# PWM_CONTROL.net
KiCad netlist of a schematic drawn in Altium Designer
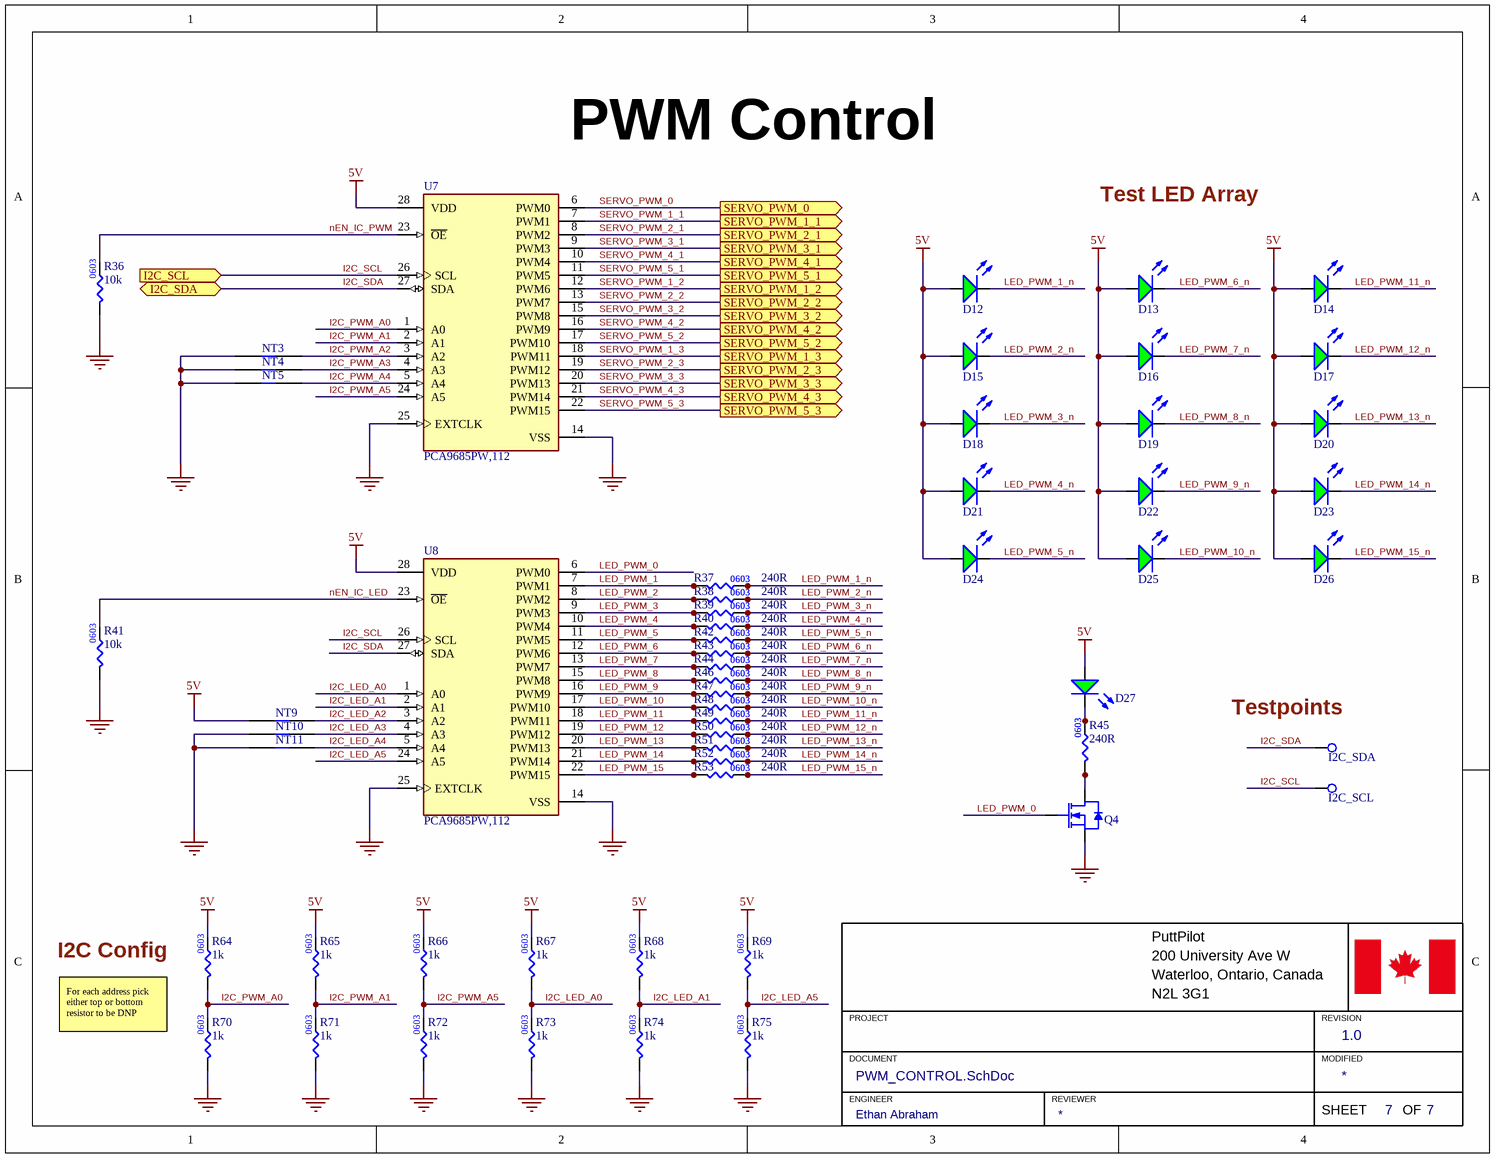
[diagram p0: PWM_CONTROL.SchDoc]

(export (version "E")
  (design (tool "Eeschema 10.0.6"))
  (components
    (comp (ref "D12")
      (value "LTST-C191KGKT")
      (footprint ".LED_0603")
      (description "LED GREEN 2V 0603")
      (fields (field (name "MANUFACTURER") "Vishay Lite-On"))
      (libsource (lib "PuttPilot") (part "LTST-C191KGKT"))
    )
    (comp (ref "D13")
      (value "LTST-C191KGKT")
      (footprint ".LED_0603")
      (description "LED GREEN 2V 0603")
      (fields (field (name "MANUFACTURER") "Vishay Lite-On"))
      (libsource (lib "PuttPilot") (part "LTST-C191KGKT"))
    )
    (comp (ref "D14")
      (value "LTST-C191KGKT")
      (footprint ".LED_0603")
      (description "LED GREEN 2V 0603")
      (fields (field (name "MANUFACTURER") "Vishay Lite-On"))
      (libsource (lib "PuttPilot") (part "LTST-C191KGKT"))
    )
    (comp (ref "D15")
      (value "LTST-C191KGKT")
      (footprint ".LED_0603")
      (description "LED GREEN 2V 0603")
      (fields (field (name "MANUFACTURER") "Vishay Lite-On"))
      (libsource (lib "PuttPilot") (part "LTST-C191KGKT"))
    )
    (comp (ref "D16")
      (value "LTST-C191KGKT")
      (footprint ".LED_0603")
      (description "LED GREEN 2V 0603")
      (fields (field (name "MANUFACTURER") "Vishay Lite-On"))
      (libsource (lib "PuttPilot") (part "LTST-C191KGKT"))
    )
    (comp (ref "D17")
      (value "LTST-C191KGKT")
      (footprint ".LED_0603")
      (description "LED GREEN 2V 0603")
      (fields (field (name "MANUFACTURER") "Vishay Lite-On"))
      (libsource (lib "PuttPilot") (part "LTST-C191KGKT"))
    )
    (comp (ref "D18")
      (value "LTST-C191KGKT")
      (footprint ".LED_0603")
      (description "LED GREEN 2V 0603")
      (fields (field (name "MANUFACTURER") "Vishay Lite-On"))
      (libsource (lib "PuttPilot") (part "LTST-C191KGKT"))
    )
    (comp (ref "D19")
      (value "LTST-C191KGKT")
      (footprint ".LED_0603")
      (description "LED GREEN 2V 0603")
      (fields (field (name "MANUFACTURER") "Vishay Lite-On"))
      (libsource (lib "PuttPilot") (part "LTST-C191KGKT"))
    )
    (comp (ref "D20")
      (value "LTST-C191KGKT")
      (footprint ".LED_0603")
      (description "LED GREEN 2V 0603")
      (fields (field (name "MANUFACTURER") "Vishay Lite-On"))
      (libsource (lib "PuttPilot") (part "LTST-C191KGKT"))
    )
    (comp (ref "D21")
      (value "LTST-C191KGKT")
      (footprint ".LED_0603")
      (description "LED GREEN 2V 0603")
      (fields (field (name "MANUFACTURER") "Vishay Lite-On"))
      (libsource (lib "PuttPilot") (part "LTST-C191KGKT"))
    )
    (comp (ref "D22")
      (value "LTST-C191KGKT")
      (footprint ".LED_0603")
      (description "LED GREEN 2V 0603")
      (fields (field (name "MANUFACTURER") "Vishay Lite-On"))
      (libsource (lib "PuttPilot") (part "LTST-C191KGKT"))
    )
    (comp (ref "D23")
      (value "LTST-C191KGKT")
      (footprint ".LED_0603")
      (description "LED GREEN 2V 0603")
      (fields (field (name "MANUFACTURER") "Vishay Lite-On"))
      (libsource (lib "PuttPilot") (part "LTST-C191KGKT"))
    )
    (comp (ref "D24")
      (value "LTST-C191KGKT")
      (footprint ".LED_0603")
      (description "LED GREEN 2V 0603")
      (fields (field (name "MANUFACTURER") "Vishay Lite-On"))
      (libsource (lib "PuttPilot") (part "LTST-C191KGKT"))
    )
    (comp (ref "D25")
      (value "LTST-C191KGKT")
      (footprint ".LED_0603")
      (description "LED GREEN 2V 0603")
      (fields (field (name "MANUFACTURER") "Vishay Lite-On"))
      (libsource (lib "PuttPilot") (part "LTST-C191KGKT"))
    )
    (comp (ref "D26")
      (value "LTST-C191KGKT")
      (footprint ".LED_0603")
      (description "LED GREEN 2V 0603")
      (fields (field (name "MANUFACTURER") "Vishay Lite-On"))
      (libsource (lib "PuttPilot") (part "LTST-C191KGKT"))
    )
    (comp (ref "D27")
      (value "LTST-C191KGKT")
      (footprint ".LED_0603")
      (description "LED GREEN 2V 0603")
      (fields (field (name "MANUFACTURER") "Vishay Lite-On"))
      (libsource (lib "PuttPilot") (part "LTST-C191KGKT"))
    )
    (comp (ref "I2C_SCL")
      (value "RCWCTE")
      (footprint "RCWCTE")
      (description "SMT Test Point")
      (fields (field (name "MANUFACTURER") "KOA Speer"))
      (libsource (lib "PuttPilot") (part "RCWCTE"))
    )
    (comp (ref "I2C_SDA")
      (value "RCWCTE")
      (footprint "RCWCTE")
      (description "SMT Test Point")
      (fields (field (name "MANUFACTURER") "KOA Speer"))
      (libsource (lib "PuttPilot") (part "RCWCTE"))
    )
    (comp (ref "NT3")
      (value ".NET_TIE")
      (footprint ".NET_TIE")
      (description ".GENERIC NET TIE")
      (libsource (lib "PuttPilot") (part ".NET_TIE"))
    )
    (comp (ref "NT4")
      (value ".NET_TIE")
      (footprint ".NET_TIE")
      (description ".GENERIC NET TIE")
      (libsource (lib "PuttPilot") (part ".NET_TIE"))
    )
    (comp (ref "NT5")
      (value ".NET_TIE")
      (footprint ".NET_TIE")
      (description ".GENERIC NET TIE")
      (libsource (lib "PuttPilot") (part ".NET_TIE"))
    )
    (comp (ref "NT9")
      (value ".NET_TIE")
      (footprint ".NET_TIE")
      (description ".GENERIC NET TIE")
      (libsource (lib "PuttPilot") (part ".NET_TIE"))
    )
    (comp (ref "NT10")
      (value ".NET_TIE")
      (footprint ".NET_TIE")
      (description ".GENERIC NET TIE")
      (libsource (lib "PuttPilot") (part ".NET_TIE"))
    )
    (comp (ref "NT11")
      (value ".NET_TIE")
      (footprint ".NET_TIE")
      (description ".GENERIC NET TIE")
      (libsource (lib "PuttPilot") (part ".NET_TIE"))
    )
    (comp (ref "Q4")
      (value "DMN6140L-7")
      (footprint ".SOT-23-3")
      (description "MOSFET N-CH 60V 1.6A SOT-23")
      (fields (field (name "MANUFACTURER") "Diodes"))
      (libsource (lib "PuttPilot") (part "DMN6140L-7"))
    )
    (comp (ref "R36")
      (value "RC0603FR-0710KL")
      (footprint ".RES_0603")
      (description "RES 10K OHM 0603")
      (fields
        (field (name "MANUFACTURER") "Yageo")
        (field (name "TOLERANCE") "1%")
        (field (name "RESISTANCE") "10k")
      )
      (libsource (lib "PuttPilot") (part "RC0603FR-0710KL"))
    )
    (comp (ref "R37")
      (value "RC0603FR-07240RL")
      (footprint ".RES_0603")
      (description "RES 240 OHM 0603")
      (fields
        (field (name "MANUFACTURER") "Yageo")
        (field (name "TOLERANCE") "1%")
        (field (name "RESISTANCE") "240R")
      )
      (libsource (lib "PuttPilot") (part "RC0603FR-07240RL"))
    )
    (comp (ref "R38")
      (value "RC0603FR-07240RL")
      (footprint ".RES_0603")
      (description "RES 240 OHM 0603")
      (fields
        (field (name "MANUFACTURER") "Yageo")
        (field (name "TOLERANCE") "1%")
        (field (name "RESISTANCE") "240R")
      )
      (libsource (lib "PuttPilot") (part "RC0603FR-07240RL"))
    )
    (comp (ref "R39")
      (value "RC0603FR-07240RL")
      (footprint ".RES_0603")
      (description "RES 240 OHM 0603")
      (fields
        (field (name "MANUFACTURER") "Yageo")
        (field (name "TOLERANCE") "1%")
        (field (name "RESISTANCE") "240R")
      )
      (libsource (lib "PuttPilot") (part "RC0603FR-07240RL"))
    )
    (comp (ref "R40")
      (value "RC0603FR-07240RL")
      (footprint ".RES_0603")
      (description "RES 240 OHM 0603")
      (fields
        (field (name "MANUFACTURER") "Yageo")
        (field (name "TOLERANCE") "1%")
        (field (name "RESISTANCE") "240R")
      )
      (libsource (lib "PuttPilot") (part "RC0603FR-07240RL"))
    )
    (comp (ref "R41")
      (value "RC0603FR-0710KL")
      (footprint ".RES_0603")
      (description "RES 10K OHM 0603")
      (fields
        (field (name "MANUFACTURER") "Yageo")
        (field (name "TOLERANCE") "1%")
        (field (name "RESISTANCE") "10k")
      )
      (libsource (lib "PuttPilot") (part "RC0603FR-0710KL"))
    )
    (comp (ref "R42")
      (value "RC0603FR-07240RL")
      (footprint ".RES_0603")
      (description "RES 240 OHM 0603")
      (fields
        (field (name "MANUFACTURER") "Yageo")
        (field (name "TOLERANCE") "1%")
        (field (name "RESISTANCE") "240R")
      )
      (libsource (lib "PuttPilot") (part "RC0603FR-07240RL"))
    )
    (comp (ref "R43")
      (value "RC0603FR-07240RL")
      (footprint ".RES_0603")
      (description "RES 240 OHM 0603")
      (fields
        (field (name "MANUFACTURER") "Yageo")
        (field (name "TOLERANCE") "1%")
        (field (name "RESISTANCE") "240R")
      )
      (libsource (lib "PuttPilot") (part "RC0603FR-07240RL"))
    )
    (comp (ref "R44")
      (value "RC0603FR-07240RL")
      (footprint ".RES_0603")
      (description "RES 240 OHM 0603")
      (fields
        (field (name "MANUFACTURER") "Yageo")
        (field (name "TOLERANCE") "1%")
        (field (name "RESISTANCE") "240R")
      )
      (libsource (lib "PuttPilot") (part "RC0603FR-07240RL"))
    )
    (comp (ref "R45")
      (value "RC0603FR-07240RL")
      (footprint ".RES_0603")
      (description "RES 240 OHM 0603")
      (fields
        (field (name "MANUFACTURER") "Yageo")
        (field (name "TOLERANCE") "1%")
        (field (name "RESISTANCE") "240R")
      )
      (libsource (lib "PuttPilot") (part "RC0603FR-07240RL"))
    )
    (comp (ref "R46")
      (value "RC0603FR-07240RL")
      (footprint ".RES_0603")
      (description "RES 240 OHM 0603")
      (fields
        (field (name "MANUFACTURER") "Yageo")
        (field (name "TOLERANCE") "1%")
        (field (name "RESISTANCE") "240R")
      )
      (libsource (lib "PuttPilot") (part "RC0603FR-07240RL"))
    )
    (comp (ref "R47")
      (value "RC0603FR-07240RL")
      (footprint ".RES_0603")
      (description "RES 240 OHM 0603")
      (fields
        (field (name "MANUFACTURER") "Yageo")
        (field (name "TOLERANCE") "1%")
        (field (name "RESISTANCE") "240R")
      )
      (libsource (lib "PuttPilot") (part "RC0603FR-07240RL"))
    )
    (comp (ref "R48")
      (value "RC0603FR-07240RL")
      (footprint ".RES_0603")
      (description "RES 240 OHM 0603")
      (fields
        (field (name "MANUFACTURER") "Yageo")
        (field (name "TOLERANCE") "1%")
        (field (name "RESISTANCE") "240R")
      )
      (libsource (lib "PuttPilot") (part "RC0603FR-07240RL"))
    )
    (comp (ref "R49")
      (value "RC0603FR-07240RL")
      (footprint ".RES_0603")
      (description "RES 240 OHM 0603")
      (fields
        (field (name "MANUFACTURER") "Yageo")
        (field (name "TOLERANCE") "1%")
        (field (name "RESISTANCE") "240R")
      )
      (libsource (lib "PuttPilot") (part "RC0603FR-07240RL"))
    )
    (comp (ref "R50")
      (value "RC0603FR-07240RL")
      (footprint ".RES_0603")
      (description "RES 240 OHM 0603")
      (fields
        (field (name "MANUFACTURER") "Yageo")
        (field (name "TOLERANCE") "1%")
        (field (name "RESISTANCE") "240R")
      )
      (libsource (lib "PuttPilot") (part "RC0603FR-07240RL"))
    )
    (comp (ref "R51")
      (value "RC0603FR-07240RL")
      (footprint ".RES_0603")
      (description "RES 240 OHM 0603")
      (fields
        (field (name "MANUFACTURER") "Yageo")
        (field (name "TOLERANCE") "1%")
        (field (name "RESISTANCE") "240R")
      )
      (libsource (lib "PuttPilot") (part "RC0603FR-07240RL"))
    )
    (comp (ref "R52")
      (value "RC0603FR-07240RL")
      (footprint ".RES_0603")
      (description "RES 240 OHM 0603")
      (fields
        (field (name "MANUFACTURER") "Yageo")
        (field (name "TOLERANCE") "1%")
        (field (name "RESISTANCE") "240R")
      )
      (libsource (lib "PuttPilot") (part "RC0603FR-07240RL"))
    )
    (comp (ref "R53")
      (value "RC0603FR-07240RL")
      (footprint ".RES_0603")
      (description "RES 240 OHM 0603")
      (fields
        (field (name "MANUFACTURER") "Yageo")
        (field (name "TOLERANCE") "1%")
        (field (name "RESISTANCE") "240R")
      )
      (libsource (lib "PuttPilot") (part "RC0603FR-07240RL"))
    )
    (comp (ref "R64")
      (value "RC0603FR-071KL")
      (footprint ".RES_0603")
      (description "RES 1K OHM 0603")
      (fields
        (field (name "MANUFACTURER") "Yageo")
        (field (name "TOLERANCE") "1%")
        (field (name "RESISTANCE") "1k")
      )
      (libsource (lib "PuttPilot") (part "RC0603FR-071KL"))
    )
    (comp (ref "R65")
      (value "RC0603FR-071KL")
      (footprint ".RES_0603")
      (description "RES 1K OHM 0603")
      (fields
        (field (name "MANUFACTURER") "Yageo")
        (field (name "TOLERANCE") "1%")
        (field (name "RESISTANCE") "1k")
      )
      (libsource (lib "PuttPilot") (part "RC0603FR-071KL"))
    )
    (comp (ref "R66")
      (value "RC0603FR-071KL")
      (footprint ".RES_0603")
      (description "RES 1K OHM 0603")
      (fields
        (field (name "MANUFACTURER") "Yageo")
        (field (name "TOLERANCE") "1%")
        (field (name "RESISTANCE") "1k")
      )
      (libsource (lib "PuttPilot") (part "RC0603FR-071KL"))
    )
    (comp (ref "R67")
      (value "RC0603FR-071KL")
      (footprint ".RES_0603")
      (description "RES 1K OHM 0603")
      (fields
        (field (name "MANUFACTURER") "Yageo")
        (field (name "TOLERANCE") "1%")
        (field (name "RESISTANCE") "1k")
      )
      (libsource (lib "PuttPilot") (part "RC0603FR-071KL"))
    )
    (comp (ref "R68")
      (value "RC0603FR-071KL")
      (footprint ".RES_0603")
      (description "RES 1K OHM 0603")
      (fields
        (field (name "MANUFACTURER") "Yageo")
        (field (name "TOLERANCE") "1%")
        (field (name "RESISTANCE") "1k")
      )
      (libsource (lib "PuttPilot") (part "RC0603FR-071KL"))
    )
    (comp (ref "R69")
      (value "RC0603FR-071KL")
      (footprint ".RES_0603")
      (description "RES 1K OHM 0603")
      (fields
        (field (name "MANUFACTURER") "Yageo")
        (field (name "TOLERANCE") "1%")
        (field (name "RESISTANCE") "1k")
      )
      (libsource (lib "PuttPilot") (part "RC0603FR-071KL"))
    )
    (comp (ref "R70")
      (value "RC0603FR-071KL")
      (footprint ".RES_0603")
      (description "RES 1K OHM 0603")
      (fields
        (field (name "MANUFACTURER") "Yageo")
        (field (name "TOLERANCE") "1%")
        (field (name "RESISTANCE") "1k")
      )
      (libsource (lib "PuttPilot") (part "RC0603FR-071KL"))
    )
    (comp (ref "R71")
      (value "RC0603FR-071KL")
      (footprint ".RES_0603")
      (description "RES 1K OHM 0603")
      (fields
        (field (name "MANUFACTURER") "Yageo")
        (field (name "TOLERANCE") "1%")
        (field (name "RESISTANCE") "1k")
      )
      (libsource (lib "PuttPilot") (part "RC0603FR-071KL"))
    )
    (comp (ref "R72")
      (value "RC0603FR-071KL")
      (footprint ".RES_0603")
      (description "RES 1K OHM 0603")
      (fields
        (field (name "MANUFACTURER") "Yageo")
        (field (name "TOLERANCE") "1%")
        (field (name "RESISTANCE") "1k")
      )
      (libsource (lib "PuttPilot") (part "RC0603FR-071KL"))
    )
    (comp (ref "R73")
      (value "RC0603FR-071KL")
      (footprint ".RES_0603")
      (description "RES 1K OHM 0603")
      (fields
        (field (name "MANUFACTURER") "Yageo")
        (field (name "TOLERANCE") "1%")
        (field (name "RESISTANCE") "1k")
      )
      (libsource (lib "PuttPilot") (part "RC0603FR-071KL"))
    )
    (comp (ref "R74")
      (value "RC0603FR-071KL")
      (footprint ".RES_0603")
      (description "RES 1K OHM 0603")
      (fields
        (field (name "MANUFACTURER") "Yageo")
        (field (name "TOLERANCE") "1%")
        (field (name "RESISTANCE") "1k")
      )
      (libsource (lib "PuttPilot") (part "RC0603FR-071KL"))
    )
    (comp (ref "R75")
      (value "RC0603FR-071KL")
      (footprint ".RES_0603")
      (description "RES 1K OHM 0603")
      (fields
        (field (name "MANUFACTURER") "Yageo")
        (field (name "TOLERANCE") "1%")
        (field (name "RESISTANCE") "1k")
      )
      (libsource (lib "PuttPilot") (part "RC0603FR-071KL"))
    )
    (comp (ref "U7")
      (value "PCA9685PW,112")
      (footprint "PCA9685PW,112")
      (description "I2C LED Driver")
      (fields (field (name "MANUFACTURER") "NXP Semiconductors"))
      (libsource (lib "PuttPilot") (part "PCA9685PW,112"))
    )
    (comp (ref "U8")
      (value "PCA9685PW,112")
      (footprint "PCA9685PW,112")
      (description "I2C LED Driver")
      (fields (field (name "MANUFACTURER") "NXP Semiconductors"))
      (libsource (lib "PuttPilot") (part "PCA9685PW,112"))
    )
  )
  (nets
    (net (code "1") (name "/I2C_LED_A0") (class "Default")
      (node (ref "R67") (pin "1") (pinfunction "1_1") (pintype "passive"))
      (node (ref "R73") (pin "2") (pinfunction "2_2") (pintype "passive"))
      (node (ref "U8") (pin "1") (pinfunction "A0_1") (pintype "input"))
    )
    (net (code "2") (name "/I2C_LED_A1") (class "Default")
      (node (ref "R68") (pin "1") (pinfunction "1_1") (pintype "passive"))
      (node (ref "R74") (pin "2") (pinfunction "2_2") (pintype "passive"))
      (node (ref "U8") (pin "2") (pinfunction "A1_2") (pintype "input"))
    )
    (net (code "3") (name "/I2C_LED_A2") (class "Default")
      (node (ref "NT9") (pin "2") (pinfunction "2_2") (pintype "passive"))
      (node (ref "U8") (pin "3") (pinfunction "A2_3") (pintype "input"))
    )
    (net (code "4") (name "/I2C_LED_A3") (class "Default")
      (node (ref "NT10") (pin "2") (pinfunction "2_2") (pintype "passive"))
      (node (ref "U8") (pin "4") (pinfunction "A3_4") (pintype "input"))
    )
    (net (code "5") (name "/I2C_LED_A4") (class "Default")
      (node (ref "NT11") (pin "2") (pinfunction "2_2") (pintype "passive"))
      (node (ref "U8") (pin "5") (pinfunction "A4_5") (pintype "input"))
    )
    (net (code "6") (name "/I2C_LED_A5") (class "Default")
      (node (ref "R69") (pin "1") (pinfunction "1_1") (pintype "passive"))
      (node (ref "R75") (pin "2") (pinfunction "2_2") (pintype "passive"))
      (node (ref "U8") (pin "24") (pinfunction "A5_24") (pintype "input"))
    )
    (net (code "7") (name "/I2C_PWM_A0") (class "Default")
      (node (ref "R64") (pin "1") (pinfunction "1_1") (pintype "passive"))
      (node (ref "R70") (pin "2") (pinfunction "2_2") (pintype "passive"))
      (node (ref "U7") (pin "1") (pinfunction "A0_1") (pintype "input"))
    )
    (net (code "8") (name "/I2C_PWM_A1") (class "Default")
      (node (ref "R65") (pin "1") (pinfunction "1_1") (pintype "passive"))
      (node (ref "R71") (pin "2") (pinfunction "2_2") (pintype "passive"))
      (node (ref "U7") (pin "2") (pinfunction "A1_2") (pintype "input"))
    )
    (net (code "9") (name "/I2C_PWM_A2") (class "Default")
      (node (ref "NT3") (pin "2") (pinfunction "2_2") (pintype "passive"))
      (node (ref "U7") (pin "3") (pinfunction "A2_3") (pintype "input"))
    )
    (net (code "10") (name "/I2C_PWM_A3") (class "Default")
      (node (ref "NT4") (pin "2") (pinfunction "2_2") (pintype "passive"))
      (node (ref "U7") (pin "4") (pinfunction "A3_4") (pintype "input"))
    )
    (net (code "11") (name "/I2C_PWM_A4") (class "Default")
      (node (ref "NT5") (pin "2") (pinfunction "2_2") (pintype "passive"))
      (node (ref "U7") (pin "5") (pinfunction "A4_5") (pintype "input"))
    )
    (net (code "12") (name "/I2C_PWM_A5") (class "Default")
      (node (ref "R66") (pin "1") (pinfunction "1_1") (pintype "passive"))
      (node (ref "R72") (pin "2") (pinfunction "2_2") (pintype "passive"))
      (node (ref "U7") (pin "24") (pinfunction "A5_24") (pintype "input"))
    )
    (net (code "13") (name "/I2C_SCL") (class "Default")
      (node (ref "I2C_SCL") (pin "1") (pinfunction "1_1") (pintype "passive"))
      (node (ref "U7") (pin "26") (pinfunction "SCL_26") (pintype "input"))
      (node (ref "U8") (pin "26") (pinfunction "SCL_26") (pintype "input"))
    )
    (net (code "14") (name "/I2C_SDA") (class "Default")
      (node (ref "I2C_SDA") (pin "1") (pinfunction "1_1") (pintype "passive"))
      (node (ref "U7") (pin "27") (pinfunction "SDA_27") (pintype "bidirectional"))
      (node (ref "U8") (pin "27") (pinfunction "SDA_27") (pintype "bidirectional"))
    )
    (net (code "15") (name "/LED_PWM_0") (class "Default")
      (node (ref "Q4") (pin "1") (pinfunction "Gate_1") (pintype "passive"))
      (node (ref "U8") (pin "6") (pinfunction "PWM0_6") (pintype "tri_state"))
    )
    (net (code "16") (name "/LED_PWM_1") (class "Default")
      (node (ref "R37") (pin "1") (pinfunction "1_1") (pintype "passive"))
      (node (ref "U8") (pin "7") (pinfunction "PWM1_7") (pintype "tri_state"))
    )
    (net (code "17") (name "/LED_PWM_1_n") (class "Default")
      (node (ref "D12") (pin "2") (pinfunction "K_2") (pintype "passive"))
      (node (ref "R37") (pin "2") (pinfunction "2_2") (pintype "passive"))
    )
    (net (code "18") (name "/LED_PWM_2") (class "Default")
      (node (ref "R38") (pin "1") (pinfunction "1_1") (pintype "passive"))
      (node (ref "U8") (pin "8") (pinfunction "PWM2_8") (pintype "tri_state"))
    )
    (net (code "19") (name "/LED_PWM_2_n") (class "Default")
      (node (ref "D15") (pin "2") (pinfunction "K_2") (pintype "passive"))
      (node (ref "R38") (pin "2") (pinfunction "2_2") (pintype "passive"))
    )
    (net (code "20") (name "/LED_PWM_3") (class "Default")
      (node (ref "R39") (pin "1") (pinfunction "1_1") (pintype "passive"))
      (node (ref "U8") (pin "9") (pinfunction "PWM3_9") (pintype "tri_state"))
    )
    (net (code "21") (name "/LED_PWM_3_n") (class "Default")
      (node (ref "D18") (pin "2") (pinfunction "K_2") (pintype "passive"))
      (node (ref "R39") (pin "2") (pinfunction "2_2") (pintype "passive"))
    )
    (net (code "22") (name "/LED_PWM_4") (class "Default")
      (node (ref "R40") (pin "1") (pinfunction "1_1") (pintype "passive"))
      (node (ref "U8") (pin "10") (pinfunction "PWM4_10") (pintype "tri_state"))
    )
    (net (code "23") (name "/LED_PWM_4_n") (class "Default")
      (node (ref "D21") (pin "2") (pinfunction "K_2") (pintype "passive"))
      (node (ref "R40") (pin "2") (pinfunction "2_2") (pintype "passive"))
    )
    (net (code "24") (name "/LED_PWM_5") (class "Default")
      (node (ref "R42") (pin "1") (pinfunction "1_1") (pintype "passive"))
      (node (ref "U8") (pin "11") (pinfunction "PWM5_11") (pintype "tri_state"))
    )
    (net (code "25") (name "/LED_PWM_5_n") (class "Default")
      (node (ref "D24") (pin "2") (pinfunction "K_2") (pintype "passive"))
      (node (ref "R42") (pin "2") (pinfunction "2_2") (pintype "passive"))
    )
    (net (code "26") (name "/LED_PWM_6") (class "Default")
      (node (ref "R43") (pin "1") (pinfunction "1_1") (pintype "passive"))
      (node (ref "U8") (pin "12") (pinfunction "PWM6_12") (pintype "tri_state"))
    )
    (net (code "27") (name "/LED_PWM_6_n") (class "Default")
      (node (ref "D13") (pin "2") (pinfunction "K_2") (pintype "passive"))
      (node (ref "R43") (pin "2") (pinfunction "2_2") (pintype "passive"))
    )
    (net (code "28") (name "/LED_PWM_7") (class "Default")
      (node (ref "R44") (pin "1") (pinfunction "1_1") (pintype "passive"))
      (node (ref "U8") (pin "13") (pinfunction "PWM7_13") (pintype "tri_state"))
    )
    (net (code "29") (name "/LED_PWM_7_n") (class "Default")
      (node (ref "D16") (pin "2") (pinfunction "K_2") (pintype "passive"))
      (node (ref "R44") (pin "2") (pinfunction "2_2") (pintype "passive"))
    )
    (net (code "30") (name "/LED_PWM_8") (class "Default")
      (node (ref "R46") (pin "1") (pinfunction "1_1") (pintype "passive"))
      (node (ref "U8") (pin "15") (pinfunction "PWM8_15") (pintype "tri_state"))
    )
    (net (code "31") (name "/LED_PWM_8_n") (class "Default")
      (node (ref "D19") (pin "2") (pinfunction "K_2") (pintype "passive"))
      (node (ref "R46") (pin "2") (pinfunction "2_2") (pintype "passive"))
    )
    (net (code "32") (name "/LED_PWM_9") (class "Default")
      (node (ref "R47") (pin "1") (pinfunction "1_1") (pintype "passive"))
      (node (ref "U8") (pin "16") (pinfunction "PWM9_16") (pintype "tri_state"))
    )
    (net (code "33") (name "/LED_PWM_9_n") (class "Default")
      (node (ref "D22") (pin "2") (pinfunction "K_2") (pintype "passive"))
      (node (ref "R47") (pin "2") (pinfunction "2_2") (pintype "passive"))
    )
    (net (code "34") (name "/LED_PWM_10") (class "Default")
      (node (ref "R48") (pin "1") (pinfunction "1_1") (pintype "passive"))
      (node (ref "U8") (pin "17") (pinfunction "PWM10_17") (pintype "tri_state"))
    )
    (net (code "35") (name "/LED_PWM_10_n") (class "Default")
      (node (ref "D25") (pin "2") (pinfunction "K_2") (pintype "passive"))
      (node (ref "R48") (pin "2") (pinfunction "2_2") (pintype "passive"))
    )
    (net (code "36") (name "/LED_PWM_11") (class "Default")
      (node (ref "R49") (pin "1") (pinfunction "1_1") (pintype "passive"))
      (node (ref "U8") (pin "18") (pinfunction "PWM11_18") (pintype "tri_state"))
    )
    (net (code "37") (name "/LED_PWM_11_n") (class "Default")
      (node (ref "D14") (pin "2") (pinfunction "K_2") (pintype "passive"))
      (node (ref "R49") (pin "2") (pinfunction "2_2") (pintype "passive"))
    )
    (net (code "38") (name "/LED_PWM_12") (class "Default")
      (node (ref "R50") (pin "1") (pinfunction "1_1") (pintype "passive"))
      (node (ref "U8") (pin "19") (pinfunction "PWM12_19") (pintype "tri_state"))
    )
    (net (code "39") (name "/LED_PWM_12_n") (class "Default")
      (node (ref "D17") (pin "2") (pinfunction "K_2") (pintype "passive"))
      (node (ref "R50") (pin "2") (pinfunction "2_2") (pintype "passive"))
    )
    (net (code "40") (name "/LED_PWM_13") (class "Default")
      (node (ref "R51") (pin "1") (pinfunction "1_1") (pintype "passive"))
      (node (ref "U8") (pin "20") (pinfunction "PWM13_20") (pintype "tri_state"))
    )
    (net (code "41") (name "/LED_PWM_13_n") (class "Default")
      (node (ref "D20") (pin "2") (pinfunction "K_2") (pintype "passive"))
      (node (ref "R51") (pin "2") (pinfunction "2_2") (pintype "passive"))
    )
    (net (code "42") (name "/LED_PWM_14") (class "Default")
      (node (ref "R52") (pin "1") (pinfunction "1_1") (pintype "passive"))
      (node (ref "U8") (pin "21") (pinfunction "PWM14_21") (pintype "tri_state"))
    )
    (net (code "43") (name "/LED_PWM_14_n") (class "Default")
      (node (ref "D23") (pin "2") (pinfunction "K_2") (pintype "passive"))
      (node (ref "R52") (pin "2") (pinfunction "2_2") (pintype "passive"))
    )
    (net (code "44") (name "/LED_PWM_15") (class "Default")
      (node (ref "R53") (pin "1") (pinfunction "1_1") (pintype "passive"))
      (node (ref "U8") (pin "22") (pinfunction "PWM15_22") (pintype "tri_state"))
    )
    (net (code "45") (name "/LED_PWM_15_n") (class "Default")
      (node (ref "D26") (pin "2") (pinfunction "K_2") (pintype "passive"))
      (node (ref "R53") (pin "2") (pinfunction "2_2") (pintype "passive"))
    )
    (net (code "46") (name "/SERVO_PWM_0") (class "Default")
      (node (ref "U7") (pin "6") (pinfunction "PWM0_6") (pintype "tri_state"))
    )
    (net (code "47") (name "/SERVO_PWM_1_1") (class "Default")
      (node (ref "U7") (pin "7") (pinfunction "PWM1_7") (pintype "tri_state"))
    )
    (net (code "48") (name "/SERVO_PWM_1_2") (class "Default")
      (node (ref "U7") (pin "12") (pinfunction "PWM6_12") (pintype "tri_state"))
    )
    (net (code "49") (name "/SERVO_PWM_1_3") (class "Default")
      (node (ref "U7") (pin "18") (pinfunction "PWM11_18") (pintype "tri_state"))
    )
    (net (code "50") (name "/SERVO_PWM_2_1") (class "Default")
      (node (ref "U7") (pin "8") (pinfunction "PWM2_8") (pintype "tri_state"))
    )
    (net (code "51") (name "/SERVO_PWM_2_2") (class "Default")
      (node (ref "U7") (pin "13") (pinfunction "PWM7_13") (pintype "tri_state"))
    )
    (net (code "52") (name "/SERVO_PWM_2_3") (class "Default")
      (node (ref "U7") (pin "19") (pinfunction "PWM12_19") (pintype "tri_state"))
    )
    (net (code "53") (name "/SERVO_PWM_3_1") (class "Default")
      (node (ref "U7") (pin "9") (pinfunction "PWM3_9") (pintype "tri_state"))
    )
    (net (code "54") (name "/SERVO_PWM_3_2") (class "Default")
      (node (ref "U7") (pin "15") (pinfunction "PWM8_15") (pintype "tri_state"))
    )
    (net (code "55") (name "/SERVO_PWM_3_3") (class "Default")
      (node (ref "U7") (pin "20") (pinfunction "PWM13_20") (pintype "tri_state"))
    )
    (net (code "56") (name "/SERVO_PWM_4_1") (class "Default")
      (node (ref "U7") (pin "10") (pinfunction "PWM4_10") (pintype "tri_state"))
    )
    (net (code "57") (name "/SERVO_PWM_4_2") (class "Default")
      (node (ref "U7") (pin "16") (pinfunction "PWM9_16") (pintype "tri_state"))
    )
    (net (code "58") (name "/SERVO_PWM_4_3") (class "Default")
      (node (ref "U7") (pin "21") (pinfunction "PWM14_21") (pintype "tri_state"))
    )
    (net (code "59") (name "/SERVO_PWM_5_1") (class "Default")
      (node (ref "U7") (pin "11") (pinfunction "PWM5_11") (pintype "tri_state"))
    )
    (net (code "60") (name "/SERVO_PWM_5_2") (class "Default")
      (node (ref "U7") (pin "17") (pinfunction "PWM10_17") (pintype "tri_state"))
    )
    (net (code "61") (name "/SERVO_PWM_5_3") (class "Default")
      (node (ref "U7") (pin "22") (pinfunction "PWM15_22") (pintype "tri_state"))
    )
    (net (code "62") (name "/nEN_IC_LED") (class "Default")
      (node (ref "R41") (pin "2") (pinfunction "2_2") (pintype "passive"))
      (node (ref "U8") (pin "23") (pinfunction "~{OE}_23") (pintype "input"))
    )
    (net (code "63") (name "/nEN_IC_PWM") (class "Default")
      (node (ref "R36") (pin "2") (pinfunction "2_2") (pintype "passive"))
      (node (ref "U7") (pin "23") (pinfunction "~{OE}_23") (pintype "input"))
    )
    (net (code "64") (name "5V") (class "Default")
      (node (ref "D12") (pin "1") (pinfunction "A_1") (pintype "passive"))
      (node (ref "D13") (pin "1") (pinfunction "A_1") (pintype "passive"))
      (node (ref "D14") (pin "1") (pinfunction "A_1") (pintype "passive"))
      (node (ref "D15") (pin "1") (pinfunction "A_1") (pintype "passive"))
      (node (ref "D16") (pin "1") (pinfunction "A_1") (pintype "passive"))
      (node (ref "D17") (pin "1") (pinfunction "A_1") (pintype "passive"))
      (node (ref "D18") (pin "1") (pinfunction "A_1") (pintype "passive"))
      (node (ref "D19") (pin "1") (pinfunction "A_1") (pintype "passive"))
      (node (ref "D20") (pin "1") (pinfunction "A_1") (pintype "passive"))
      (node (ref "D21") (pin "1") (pinfunction "A_1") (pintype "passive"))
      (node (ref "D22") (pin "1") (pinfunction "A_1") (pintype "passive"))
      (node (ref "D23") (pin "1") (pinfunction "A_1") (pintype "passive"))
      (node (ref "D24") (pin "1") (pinfunction "A_1") (pintype "passive"))
      (node (ref "D25") (pin "1") (pinfunction "A_1") (pintype "passive"))
      (node (ref "D26") (pin "1") (pinfunction "A_1") (pintype "passive"))
      (node (ref "D27") (pin "1") (pinfunction "A_1") (pintype "passive"))
      (node (ref "NT9") (pin "1") (pinfunction "1_1") (pintype "passive"))
      (node (ref "R64") (pin "2") (pinfunction "2_2") (pintype "passive"))
      (node (ref "R65") (pin "2") (pinfunction "2_2") (pintype "passive"))
      (node (ref "R66") (pin "2") (pinfunction "2_2") (pintype "passive"))
      (node (ref "R67") (pin "2") (pinfunction "2_2") (pintype "passive"))
      (node (ref "R68") (pin "2") (pinfunction "2_2") (pintype "passive"))
      (node (ref "R69") (pin "2") (pinfunction "2_2") (pintype "passive"))
      (node (ref "U7") (pin "28") (pinfunction "VDD_28") (pintype "power_in"))
      (node (ref "U8") (pin "28") (pinfunction "VDD_28") (pintype "power_in"))
    )
    (net (code "65") (name "GND") (class "Default")
      (node (ref "NT10") (pin "1") (pinfunction "1_1") (pintype "passive"))
      (node (ref "NT11") (pin "1") (pinfunction "1_1") (pintype "passive"))
      (node (ref "NT3") (pin "1") (pinfunction "1_1") (pintype "passive"))
      (node (ref "NT4") (pin "1") (pinfunction "1_1") (pintype "passive"))
      (node (ref "NT5") (pin "1") (pinfunction "1_1") (pintype "passive"))
      (node (ref "Q4") (pin "2") (pinfunction "Source_2") (pintype "passive"))
      (node (ref "R36") (pin "1") (pinfunction "1_1") (pintype "passive"))
      (node (ref "R41") (pin "1") (pinfunction "1_1") (pintype "passive"))
      (node (ref "R70") (pin "1") (pinfunction "1_1") (pintype "passive"))
      (node (ref "R71") (pin "1") (pinfunction "1_1") (pintype "passive"))
      (node (ref "R72") (pin "1") (pinfunction "1_1") (pintype "passive"))
      (node (ref "R73") (pin "1") (pinfunction "1_1") (pintype "passive"))
      (node (ref "R74") (pin "1") (pinfunction "1_1") (pintype "passive"))
      (node (ref "R75") (pin "1") (pinfunction "1_1") (pintype "passive"))
      (node (ref "U7") (pin "14") (pinfunction "VSS_14") (pintype "power_in"))
      (node (ref "U7") (pin "25") (pinfunction "EXTCLK_25") (pintype "input"))
      (node (ref "U8") (pin "14") (pinfunction "VSS_14") (pintype "power_in"))
      (node (ref "U8") (pin "25") (pinfunction "EXTCLK_25") (pintype "input"))
    )
    (net (code "66") (name "Net-(D27-K)") (class "Default")
      (node (ref "D27") (pin "2") (pinfunction "K_2") (pintype "passive"))
      (node (ref "R45") (pin "2") (pinfunction "2_2") (pintype "passive"))
    )
    (net (code "67") (name "Net-(Q4-Drain)") (class "Default")
      (node (ref "Q4") (pin "3") (pinfunction "Drain_3") (pintype "passive"))
      (node (ref "R45") (pin "1") (pinfunction "1_1") (pintype "passive"))
    )
  )
)
